# can.net
KiCad netlist of a schematic drawn in Altium Designer
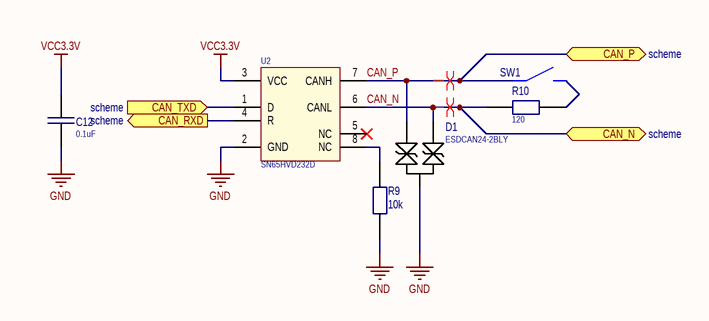
[diagram p0: can.SchDoc]

(export (version "E")
  (design (tool "Eeschema 10.0.6"))
  (components
    (comp (ref "C12")
      (value "0.1uF")
      (footprint "C_0603")
      (description "Capacitor")
      (fields (field (name "PART NUMBER") "CC0603KPX7R9BB104"))
      (libsource (lib "capacitors") (part "CAP_SMD"))
    )
    (comp (ref "D1")
      (value "ESDCAN24-2BLY")
      (footprint "diode:SOT23")
      (description "ESD")
      (libsource (lib "diode") (part "ESD_CAN"))
    )
    (comp (ref "R9")
      (value "10k")
      (footprint "R_0603")
      (description "Resistor")
      (fields (field (name "PART NUMBER") "RC0603FR-0710KL"))
      (libsource (lib "resistors") (part "RES_SMD"))
    )
    (comp (ref "R10")
      (value "120")
      (footprint "R_0603")
      (description "Resistor")
      (fields (field (name "PART NUMBER") "RC0603FR-07120RL"))
      (libsource (lib "resistors") (part "RES_SMD"))
    )
    (comp (ref "SW1")
      (value "DS1040-01RT")
      (footprint "DS1040-01RT")
      (libsource (lib "other") (part "button_dip"))
    )
    (comp (ref "U2")
      (value "SN65HVD232D")
      (footprint "SO-8_M")
      (description "CAN_transiever")
      (libsource (lib "discret_ic") (part "SN65HVD232D"))
    )
  )
  (nets
    (net (code "1") (name "/CAN_N") (class "Default")
      (node (ref "D1") (pin "2") (pinfunction "2_2") (pintype "passive"))
      (node (ref "R10") (pin "2") (pinfunction "2_2") (pintype "passive"))
      (node (ref "U2") (pin "6") (pinfunction "CANL_6") (pintype "passive"))
    )
    (net (code "2") (name "/CAN_P") (class "Default")
      (node (ref "D1") (pin "1") (pinfunction "1_1") (pintype "passive"))
      (node (ref "SW1") (pin "1") (pinfunction "1_1") (pintype "passive"))
      (node (ref "U2") (pin "7") (pinfunction "CANH_7") (pintype "passive"))
    )
    (net (code "3") (name "/CAN_RXD") (class "Default")
      (node (ref "U2") (pin "4") (pinfunction "R_4") (pintype "passive"))
    )
    (net (code "4") (name "/CAN_TXD") (class "Default")
      (node (ref "U2") (pin "1") (pinfunction "D_1") (pintype "passive"))
    )
    (net (code "5") (name "GND") (class "Default")
      (node (ref "C12") (pin "1") (pinfunction "1_1") (pintype "passive"))
      (node (ref "D1") (pin "3") (pinfunction "3_3") (pintype "passive"))
      (node (ref "R9") (pin "2") (pinfunction "2_2") (pintype "passive"))
      (node (ref "U2") (pin "2") (pinfunction "GND_2") (pintype "passive"))
    )
    (net (code "6") (name "Net-(R9-Pad1)") (class "Default")
      (node (ref "R9") (pin "1") (pinfunction "1_1") (pintype "passive"))
      (node (ref "U2") (pin "8") (pinfunction "NC_8") (pintype "passive"))
    )
    (net (code "7") (name "Net-(R10-Pad1)") (class "Default")
      (node (ref "R10") (pin "1") (pinfunction "1_1") (pintype "passive"))
      (node (ref "SW1") (pin "2") (pinfunction "2_2") (pintype "passive"))
    )
    (net (code "8") (name "VCC3.3V") (class "Default")
      (node (ref "C12") (pin "2") (pinfunction "2_2") (pintype "passive"))
      (node (ref "U2") (pin "3") (pinfunction "VCC_3") (pintype "passive"))
    )
    (net (code "9") (name "unconnected-(U2-NC-Pad5)") (class "Default")
      (node (ref "U2") (pin "5") (pinfunction "NC_5") (pintype "passive+no_connect"))
    )
  )
)
